# Metro_Mini_Rev_A.net
KiCad netlist of a schematic drawn in EAGLE
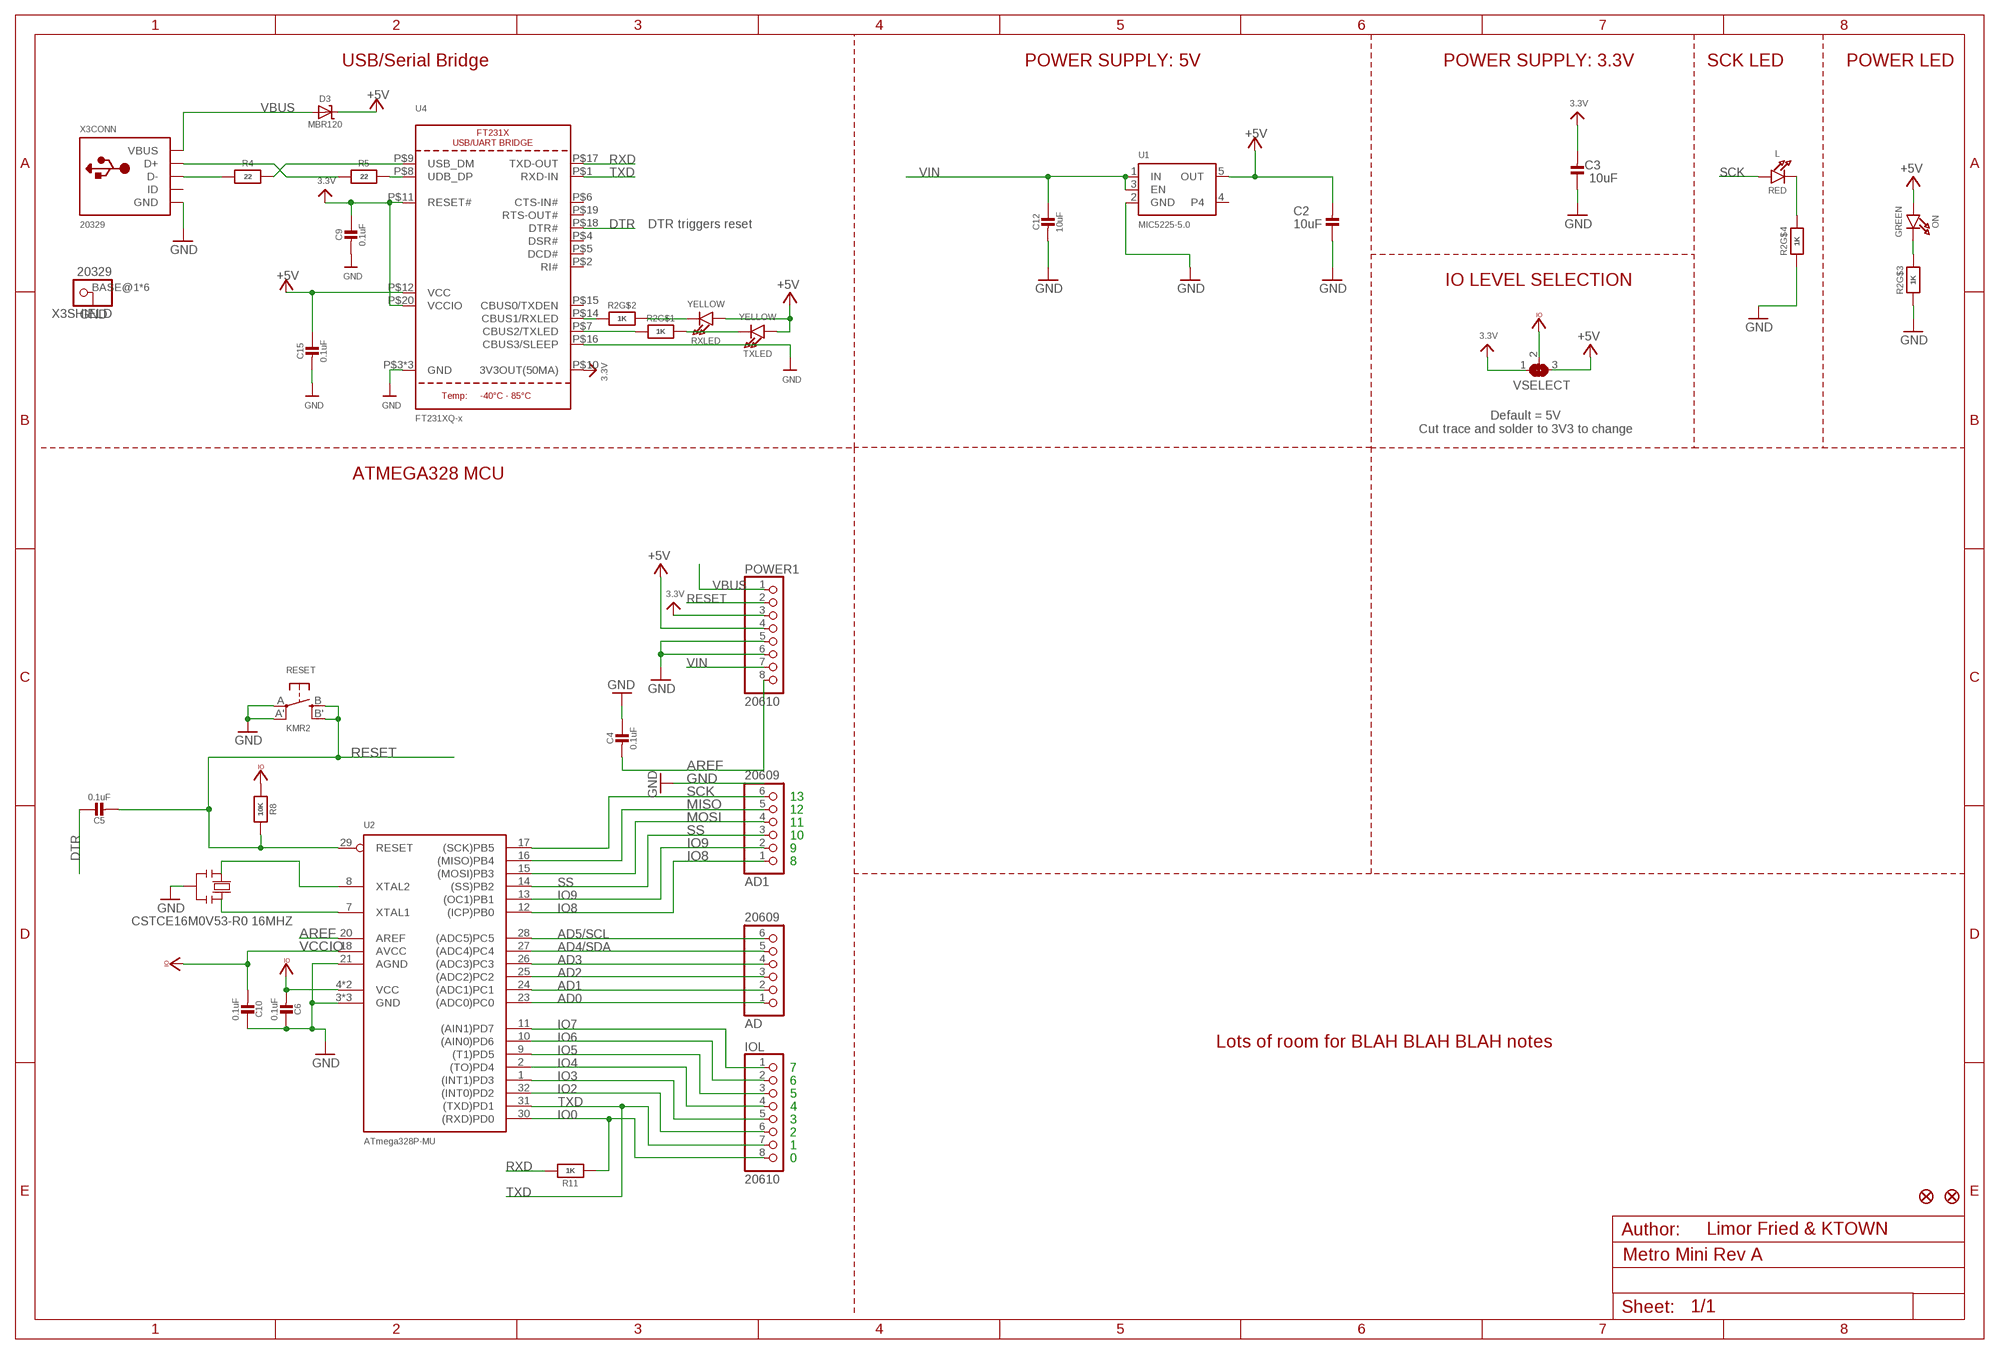
[diagram p0: schematic, sheet 1]

(export (version "E")
  (design (tool "Eeschema 10.0.6"))
  (components
    (comp (ref "AD")
      (value "20609")
      (footprint "eagle-import:1X06_ROUND")
      (libsource (lib "eagle-import") (part "HEADER-1X6ROUND"))
    )
    (comp (ref "AD1")
      (value "20609")
      (footprint "eagle-import:1X06_ROUND")
      (libsource (lib "eagle-import") (part "HEADER-1X6ROUND"))
    )
    (comp (ref "C2")
      (value "10uF")
      (footprint "eagle-import:0805-NO")
      (libsource (lib "eagle-import") (part "CAP_CERAMIC0805-NOOUTLINE"))
    )
    (comp (ref "C3")
      (value "10uF")
      (footprint "eagle-import:0805-NO")
      (libsource (lib "eagle-import") (part "CAP_CERAMIC0805-NOOUTLINE"))
    )
    (comp (ref "C4")
      (value "0.1uF")
      (footprint "eagle-import:0805-NO")
      (libsource (lib "eagle-import") (part "CAP_CERAMIC0805-NOOUTLINE"))
    )
    (comp (ref "C5")
      (value "0.1uF")
      (footprint "eagle-import:_0805MP")
      (libsource (lib "eagle-import") (part "CAP_CERAMIC_0805MP"))
    )
    (comp (ref "C6")
      (value "0.1uF")
      (footprint "eagle-import:0805-NO")
      (libsource (lib "eagle-import") (part "CAP_CERAMIC0805-NOOUTLINE"))
    )
    (comp (ref "C9")
      (value "0.1uF")
      (footprint "eagle-import:0805-NO")
      (libsource (lib "eagle-import") (part "CAP_CERAMIC0805-NOOUTLINE"))
    )
    (comp (ref "C10")
      (value "0.1uF")
      (footprint "eagle-import:0805-NO")
      (libsource (lib "eagle-import") (part "CAP_CERAMIC0805-NOOUTLINE"))
    )
    (comp (ref "C12")
      (value "10uF")
      (footprint "eagle-import:0805-NO")
      (libsource (lib "eagle-import") (part "CAP_CERAMIC0805-NOOUTLINE"))
    )
    (comp (ref "C15")
      (value "0.1uF")
      (footprint "eagle-import:0805-NO")
      (libsource (lib "eagle-import") (part "CAP_CERAMIC0805-NOOUTLINE"))
    )
    (comp (ref "D3")
      (value "MBR120")
      (footprint "eagle-import:SOD-123")
      (libsource (lib "eagle-import") (part "DIODE-SCHOTTKYSOD-123"))
    )
    (comp (ref "FD1")
      (value "FIDUCIAL\"\"")
      (footprint "eagle-import:FIDUCIAL_1MM")
      (libsource (lib "eagle-import") (part "FIDUCIAL{dblquote}{dblquote}"))
    )
    (comp (ref "FD2")
      (value "FIDUCIAL\"\"")
      (footprint "eagle-import:FIDUCIAL_1MM")
      (libsource (lib "eagle-import") (part "FIDUCIAL{dblquote}{dblquote}"))
    )
    (comp (ref "IOL")
      (value "20610")
      (footprint "eagle-import:1X08_ROUND")
      (libsource (lib "eagle-import") (part "HEADER-1X8ROUND"))
    )
    (comp (ref "L")
      (value "RED")
      (footprint "eagle-import:CHIPLED_0805_NOOUTLINE")
      (libsource (lib "eagle-import") (part "LED0805_NOOUTLINE"))
    )
    (comp (ref "ON")
      (value "GREEN")
      (footprint "eagle-import:CHIPLED_0805_NOOUTLINE")
      (libsource (lib "eagle-import") (part "LED0805_NOOUTLINE"))
    )
    (comp (ref "POWER1")
      (value "20610")
      (footprint "eagle-import:1X08_ROUND_70")
      (libsource (lib "eagle-import") (part "HEADER-1X870MIL"))
    )
    (comp (ref "R2")
      (value "1K")
      (footprint "eagle-import:RESPACK_4X0603")
      (libsource (lib "eagle-import") (part "RESISTOR_4PACK"))
    )
    (comp (ref "R4")
      (value "22")
      (footprint "eagle-import:0805-NO")
      (libsource (lib "eagle-import") (part "RESISTOR0805_NOOUTLINE"))
    )
    (comp (ref "R5")
      (value "22")
      (footprint "eagle-import:_0805MP")
      (libsource (lib "eagle-import") (part "RESISTOR_0805MP"))
    )
    (comp (ref "R8")
      (value "10K")
      (footprint "eagle-import:0805-NO")
      (libsource (lib "eagle-import") (part "RESISTOR0805_NOOUTLINE"))
    )
    (comp (ref "R11")
      (value "1K")
      (footprint "eagle-import:0805-NO")
      (libsource (lib "eagle-import") (part "RESISTOR0805_NOOUTLINE"))
    )
    (comp (ref "RESET")
      (value "KMR2")
      (footprint "eagle-import:BTN_KMR2_4.6X2.8")
      (libsource (lib "eagle-import") (part "SWITCH_TACT_SMT4.6X2.8"))
    )
    (comp (ref "RXLED")
      (value "YELLOW")
      (footprint "eagle-import:CHIPLED_0805_NOOUTLINE")
      (libsource (lib "eagle-import") (part "LED0805_NOOUTLINE"))
    )
    (comp (ref "TXLED")
      (value "YELLOW")
      (footprint "eagle-import:CHIPLED_0805_NOOUTLINE")
      (libsource (lib "eagle-import") (part "LED0805_NOOUTLINE"))
    )
    (comp (ref "U1")
      (value "MIC5225-5.0")
      (footprint "eagle-import:SOT23-5")
      (libsource (lib "eagle-import") (part "VREG_SOT23-5"))
    )
    (comp (ref "U2")
      (value "ATmega328P-MU")
      (footprint "eagle-import:MLF32-TH")
      (libsource (lib "eagle-import") (part "ATMEGA328P"))
    )
    (comp (ref "U4")
      (value "FT231XQ-x")
      (footprint "eagle-import:QFN20_4MM")
      (libsource (lib "eagle-import") (part "FT231X"))
    )
    (comp (ref "VSELECT")
      (value "SOLDERJUMPER_2WAY")
      (footprint "eagle-import:SOLDERJUMPER_2WAY_OPEN_NOPASTE")
      (libsource (lib "eagle-import") (part "SOLDERJUMPER_2WAY"))
    )
    (comp (ref "X3")
      (value "20329")
      (footprint "eagle-import:4UCONN_20329")
      (libsource (lib "eagle-import") (part "USB_W_SHIELD_20329"))
    )
    (comp (ref "Y2")
      (value "CSTCE16M0V53-R0 16MHZ")
      (footprint "eagle-import:RESONATOR")
      (libsource (lib "eagle-import") (part "RESONATORMU"))
    )
  )
  (nets
    (net (code "1") (name "+5V") (class "Default")
      (node (ref "C15") (pin "1") (pinfunction "1_1") (pintype "passive"))
      (node (ref "C2") (pin "2") (pinfunction "2_2") (pintype "passive"))
      (node (ref "D3") (pin "C") (pinfunction "C_C") (pintype "passive"))
      (node (ref "ON") (pin "A") (pinfunction "A_A") (pintype "passive"))
      (node (ref "POWER1") (pin "4") (pinfunction "4_4") (pintype "passive"))
      (node (ref "RXLED") (pin "A") (pinfunction "A_A") (pintype "passive"))
      (node (ref "TXLED") (pin "A") (pinfunction "A_A") (pintype "passive"))
      (node (ref "U1") (pin "5") (pinfunction "OUT_5") (pintype "power_in"))
      (node (ref "U4") (pin "P$12") (pinfunction "VCC_P$12") (pintype "power_in"))
      (node (ref "VSELECT") (pin "3") (pinfunction "3_3") (pintype "passive"))
    )
    (net (code "2") (name "/AD0") (class "Default")
      (node (ref "AD") (pin "1") (pinfunction "1_1") (pintype "passive"))
      (node (ref "U2") (pin "23") (pinfunction "(ADC0)PC0_23") (pintype "bidirectional"))
    )
    (net (code "3") (name "/AD1") (class "Default")
      (node (ref "AD") (pin "2") (pinfunction "2_2") (pintype "passive"))
      (node (ref "U2") (pin "24") (pinfunction "(ADC1)PC1_24") (pintype "bidirectional"))
    )
    (net (code "4") (name "/AD2") (class "Default")
      (node (ref "AD") (pin "3") (pinfunction "3_3") (pintype "passive"))
      (node (ref "U2") (pin "25") (pinfunction "(ADC2)PC2_25") (pintype "bidirectional"))
    )
    (net (code "5") (name "/AD3") (class "Default")
      (node (ref "AD") (pin "4") (pinfunction "4_4") (pintype "passive"))
      (node (ref "U2") (pin "26") (pinfunction "(ADC3)PC3_26") (pintype "bidirectional"))
    )
    (net (code "6") (name "/AD4{slash}SDA") (class "Default")
      (node (ref "AD") (pin "5") (pinfunction "5_5") (pintype "passive"))
      (node (ref "U2") (pin "27") (pinfunction "(ADC4)PC4_27") (pintype "bidirectional"))
    )
    (net (code "7") (name "/AD5{slash}SCL") (class "Default")
      (node (ref "AD") (pin "6") (pinfunction "6_6") (pintype "passive"))
      (node (ref "U2") (pin "28") (pinfunction "(ADC5)PC5_28") (pintype "bidirectional"))
    )
    (net (code "8") (name "/AREF") (class "Default")
      (node (ref "C4") (pin "2") (pinfunction "2_2") (pintype "passive"))
      (node (ref "POWER1") (pin "8") (pinfunction "8_8") (pintype "passive"))
      (node (ref "U2") (pin "20") (pinfunction "AREF_20") (pintype "power_in"))
    )
    (net (code "9") (name "/DTR") (class "Default")
      (node (ref "C5") (pin "1") (pinfunction "1_1") (pintype "passive"))
      (node (ref "U4") (pin "P$18") (pinfunction "DTR#_P$18") (pintype "output"))
    )
    (net (code "10") (name "/IO0") (class "Default")
      (node (ref "IOL") (pin "8") (pinfunction "8_8") (pintype "passive"))
      (node (ref "R11") (pin "1") (pinfunction "1_1") (pintype "passive"))
      (node (ref "U2") (pin "30") (pinfunction "(RXD)PD0_30") (pintype "bidirectional"))
    )
    (net (code "11") (name "/IO2") (class "Default")
      (node (ref "IOL") (pin "6") (pinfunction "6_6") (pintype "passive"))
      (node (ref "U2") (pin "32") (pinfunction "(INT0)PD2_32") (pintype "bidirectional"))
    )
    (net (code "12") (name "/IO3") (class "Default")
      (node (ref "IOL") (pin "5") (pinfunction "5_5") (pintype "passive"))
      (node (ref "U2") (pin "1") (pinfunction "(INT1)PD3_1") (pintype "bidirectional"))
    )
    (net (code "13") (name "/IO4") (class "Default")
      (node (ref "IOL") (pin "4") (pinfunction "4_4") (pintype "passive"))
      (node (ref "U2") (pin "2") (pinfunction "(TO)PD4_2") (pintype "bidirectional"))
    )
    (net (code "14") (name "/IO5") (class "Default")
      (node (ref "IOL") (pin "3") (pinfunction "3_3") (pintype "passive"))
      (node (ref "U2") (pin "9") (pinfunction "(T1)PD5_9") (pintype "bidirectional"))
    )
    (net (code "15") (name "/IO6") (class "Default")
      (node (ref "IOL") (pin "2") (pinfunction "2_2") (pintype "passive"))
      (node (ref "U2") (pin "10") (pinfunction "(AIN0)PD6_10") (pintype "bidirectional"))
    )
    (net (code "16") (name "/IO7") (class "Default")
      (node (ref "IOL") (pin "1") (pinfunction "1_1") (pintype "passive"))
      (node (ref "U2") (pin "11") (pinfunction "(AIN1)PD7_11") (pintype "bidirectional"))
    )
    (net (code "17") (name "/IO8") (class "Default")
      (node (ref "AD1") (pin "1") (pinfunction "1_1") (pintype "passive"))
      (node (ref "U2") (pin "12") (pinfunction "(ICP)PB0_12") (pintype "bidirectional"))
    )
    (net (code "18") (name "/IO9") (class "Default")
      (node (ref "AD1") (pin "2") (pinfunction "2_2") (pintype "passive"))
      (node (ref "U2") (pin "13") (pinfunction "(OC1)PB1_13") (pintype "bidirectional"))
    )
    (net (code "19") (name "/MISO") (class "Default")
      (node (ref "AD1") (pin "5") (pinfunction "5_5") (pintype "passive"))
      (node (ref "U2") (pin "16") (pinfunction "(MISO)PB4_16") (pintype "bidirectional"))
    )
    (net (code "20") (name "/MOSI") (class "Default")
      (node (ref "AD1") (pin "4") (pinfunction "4_4") (pintype "passive"))
      (node (ref "U2") (pin "15") (pinfunction "(MOSI)PB3_15") (pintype "bidirectional"))
    )
    (net (code "21") (name "/RESET") (class "Default")
      (node (ref "C5") (pin "2") (pinfunction "2_2") (pintype "passive"))
      (node (ref "POWER1") (pin "2") (pinfunction "2_2") (pintype "passive"))
      (node (ref "R8") (pin "1") (pinfunction "1_1") (pintype "passive"))
      (node (ref "RESET") (pin "B") (pinfunction "S_B") (pintype "passive"))
      (node (ref "RESET") (pin "B'") (pinfunction "S1_B'") (pintype "passive"))
      (node (ref "U2") (pin "29") (pinfunction "RESET_29") (pintype "bidirectional"))
    )
    (net (code "22") (name "/RXD") (class "Default")
      (node (ref "R11") (pin "2") (pinfunction "2_2") (pintype "passive"))
      (node (ref "U4") (pin "P$17") (pinfunction "TXD-OUT_P$17") (pintype "output"))
    )
    (net (code "23") (name "/SCK") (class "Default")
      (node (ref "AD1") (pin "6") (pinfunction "6_6") (pintype "passive"))
      (node (ref "L") (pin "A") (pinfunction "A_A") (pintype "passive"))
      (node (ref "U2") (pin "17") (pinfunction "(SCK)PB5_17") (pintype "bidirectional"))
    )
    (net (code "24") (name "/SS") (class "Default")
      (node (ref "AD1") (pin "3") (pinfunction "3_3") (pintype "passive"))
      (node (ref "U2") (pin "14") (pinfunction "(SS)PB2_14") (pintype "bidirectional"))
    )
    (net (code "25") (name "/TXD") (class "Default")
      (node (ref "IOL") (pin "7") (pinfunction "7_7") (pintype "passive"))
      (node (ref "U2") (pin "31") (pinfunction "(TXD)PD1_31") (pintype "bidirectional"))
      (node (ref "U4") (pin "P$1") (pinfunction "RXD-IN_P$1") (pintype "input"))
    )
    (net (code "26") (name "/VBUS") (class "Default")
      (node (ref "D3") (pin "A") (pinfunction "A_A") (pintype "passive"))
      (node (ref "POWER1") (pin "1") (pinfunction "1_1") (pintype "passive"))
      (node (ref "X3") (pin "VBUS") (pinfunction "VBUS_VBUS") (pintype "power_in"))
    )
    (net (code "27") (name "/VIN") (class "Default")
      (node (ref "C12") (pin "1") (pinfunction "1_1") (pintype "passive"))
      (node (ref "POWER1") (pin "7") (pinfunction "7_7") (pintype "passive"))
      (node (ref "U1") (pin "1") (pinfunction "IN_1") (pintype "power_in"))
      (node (ref "U1") (pin "3") (pinfunction "EN_3") (pintype "input"))
    )
    (net (code "28") (name "3.3V") (class "Default")
      (node (ref "C3") (pin "2") (pinfunction "2_2") (pintype "passive"))
      (node (ref "C9") (pin "1") (pinfunction "1_1") (pintype "passive"))
      (node (ref "POWER1") (pin "3") (pinfunction "3_3") (pintype "passive"))
      (node (ref "U4") (pin "P$10") (pinfunction "3V3OUT(50MA)_P$10") (pintype "power_in"))
      (node (ref "U4") (pin "P$11") (pinfunction "RESET#_P$11") (pintype "input"))
      (node (ref "U4") (pin "P$20") (pinfunction "VCCIO_P$20") (pintype "power_in"))
      (node (ref "VSELECT") (pin "1") (pinfunction "1_1") (pintype "passive"))
    )
    (net (code "29") (name "GND") (class "Default")
      (node (ref "C10") (pin "1") (pinfunction "1_1") (pintype "passive"))
      (node (ref "C12") (pin "2") (pinfunction "2_2") (pintype "passive"))
      (node (ref "C15") (pin "2") (pinfunction "2_2") (pintype "passive"))
      (node (ref "C2") (pin "1") (pinfunction "1_1") (pintype "passive"))
      (node (ref "C3") (pin "1") (pinfunction "1_1") (pintype "passive"))
      (node (ref "C4") (pin "1") (pinfunction "1_1") (pintype "passive"))
      (node (ref "C6") (pin "1") (pinfunction "1_1") (pintype "passive"))
      (node (ref "C9") (pin "2") (pinfunction "2_2") (pintype "passive"))
      (node (ref "POWER1") (pin "5") (pinfunction "5_5") (pintype "passive"))
      (node (ref "POWER1") (pin "6") (pinfunction "6_6") (pintype "passive"))
      (node (ref "R2") (pin "3") (pinfunction "1_3") (pintype "passive"))
      (node (ref "R2") (pin "4") (pinfunction "1_4") (pintype "passive"))
      (node (ref "RESET") (pin "A") (pinfunction "P_A") (pintype "passive"))
      (node (ref "RESET") (pin "A'") (pinfunction "P1_A'") (pintype "passive"))
      (node (ref "U1") (pin "2") (pinfunction "GND_2") (pintype "power_in"))
      (node (ref "U2") (pin "21") (pinfunction "AGND_21") (pintype "power_in"))
      (node (ref "U2") (pin "3") (pinfunction "GND_3") (pintype "power_in"))
      (node (ref "U2") (pin "5") (pinfunction "GND_5") (pintype "power_in"))
      (node (ref "U2") (pin "TH") (pinfunction "GND_TH") (pintype "power_in"))
      (node (ref "U4") (pin "P$13") (pinfunction "GND_P$13") (pintype "power_in"))
      (node (ref "U4") (pin "P$16") (pinfunction "CBUS3/SLEEP_P$16") (pintype "bidirectional"))
      (node (ref "U4") (pin "P$21") (pinfunction "GND_P$21") (pintype "power_in"))
      (node (ref "U4") (pin "P$3") (pinfunction "GND_P$3") (pintype "power_in"))
      (node (ref "X3") (pin "BASE@1") (pinfunction "1_BASE@1") (pintype "passive"))
      (node (ref "X3") (pin "BASE@2") (pinfunction "1_BASE@2") (pintype "passive"))
      (node (ref "X3") (pin "GND") (pinfunction "GND_GND") (pintype "power_in"))
      (node (ref "X3") (pin "SPRT@1") (pinfunction "1_SPRT@1") (pintype "passive"))
      (node (ref "X3") (pin "SPRT@2") (pinfunction "1_SPRT@2") (pintype "passive"))
      (node (ref "X3") (pin "SPRT@3") (pinfunction "1_SPRT@3") (pintype "passive"))
      (node (ref "X3") (pin "SPRT@4") (pinfunction "1_SPRT@4") (pintype "passive"))
      (node (ref "Y2") (pin "2") (pinfunction "2_2") (pintype "passive"))
    )
    (net (code "30") (name "Net-(R2A-2)") (class "Default")
      (node (ref "R2") (pin "8") (pinfunction "2_8") (pintype "passive"))
      (node (ref "TXLED") (pin "C") (pinfunction "C_C") (pintype "passive"))
    )
    (net (code "31") (name "Net-(R2B-1)") (class "Default")
      (node (ref "R2") (pin "2") (pinfunction "1_2") (pintype "passive"))
      (node (ref "U4") (pin "P$14") (pinfunction "CBUS1/RXLED_P$14") (pintype "bidirectional"))
    )
    (net (code "32") (name "Net-(R2B-2)") (class "Default")
      (node (ref "R2") (pin "7") (pinfunction "2_7") (pintype "passive"))
      (node (ref "RXLED") (pin "C") (pinfunction "C_C") (pintype "passive"))
    )
    (net (code "33") (name "Net-(R2C-2)") (class "Default")
      (node (ref "ON") (pin "C") (pinfunction "C_C") (pintype "passive"))
      (node (ref "R2") (pin "6") (pinfunction "2_6") (pintype "passive"))
    )
    (net (code "34") (name "Net-(R2D-2)") (class "Default")
      (node (ref "L") (pin "C") (pinfunction "C_C") (pintype "passive"))
      (node (ref "R2") (pin "5") (pinfunction "2_5") (pintype "passive"))
    )
    (net (code "35") (name "Net-(R4-Pad1)") (class "Default")
      (node (ref "R4") (pin "1") (pinfunction "1_1") (pintype "passive"))
      (node (ref "X3") (pin "D-") (pinfunction "D-_D-") (pintype "bidirectional"))
    )
    (net (code "36") (name "Net-(R5-Pad1)") (class "Default")
      (node (ref "R5") (pin "1") (pinfunction "1_1") (pintype "passive"))
      (node (ref "X3") (pin "D+") (pinfunction "D+_D+") (pintype "bidirectional"))
    )
    (net (code "37") (name "Net-(U2-XTAL1)") (class "Default")
      (node (ref "U2") (pin "7") (pinfunction "XTAL1_7") (pintype "bidirectional"))
      (node (ref "Y2") (pin "3") (pinfunction "3_3") (pintype "passive"))
    )
    (net (code "38") (name "Net-(U2-XTAL2)") (class "Default")
      (node (ref "U2") (pin "8") (pinfunction "XTAL2_8") (pintype "bidirectional"))
      (node (ref "Y2") (pin "1") (pinfunction "1_1") (pintype "passive"))
    )
    (net (code "39") (name "Net-(U4-CBUS2{slash}TXLED)") (class "Default")
      (node (ref "R2") (pin "1") (pinfunction "1_1") (pintype "passive"))
      (node (ref "U4") (pin "P$7") (pinfunction "CBUS2/TXLED_P$7") (pintype "bidirectional"))
    )
    (net (code "40") (name "Net-(U4-UDB_DP)") (class "Default")
      (node (ref "R5") (pin "2") (pinfunction "2_2") (pintype "passive"))
      (node (ref "U4") (pin "P$8") (pinfunction "UDB_DP_P$8") (pintype "input"))
    )
    (net (code "41") (name "Net-(U4-USB_DM)") (class "Default")
      (node (ref "R4") (pin "2") (pinfunction "2_2") (pintype "passive"))
      (node (ref "U4") (pin "P$9") (pinfunction "USB_DM_P$9") (pintype "input"))
    )
    (net (code "42") (name "VCCIO") (class "Default")
      (node (ref "C10") (pin "2") (pinfunction "2_2") (pintype "passive"))
      (node (ref "C6") (pin "2") (pinfunction "2_2") (pintype "passive"))
      (node (ref "R8") (pin "2") (pinfunction "2_2") (pintype "passive"))
      (node (ref "U2") (pin "18") (pinfunction "AVCC_18") (pintype "power_in"))
      (node (ref "U2") (pin "4") (pinfunction "VCC_4") (pintype "power_in"))
      (node (ref "U2") (pin "6") (pinfunction "VCC_6") (pintype "power_in"))
      (node (ref "VSELECT") (pin "2") (pinfunction "2_2") (pintype "passive"))
    )
    (net (code "43") (name "unconnected-(U1-P4-Pad4)") (class "Default")
      (node (ref "U1") (pin "4") (pinfunction "P4_4") (pintype "bidirectional"))
    )
    (net (code "44") (name "unconnected-(U4-CBUS0{slash}TXDEN-PadP$15)") (class "Default")
      (node (ref "U4") (pin "P$15") (pinfunction "CBUS0/TXDEN_P$15") (pintype "bidirectional"))
    )
    (net (code "45") (name "unconnected-(U4-CTS-IN#-PadP$6)") (class "Default")
      (node (ref "U4") (pin "P$6") (pinfunction "CTS-IN#_P$6") (pintype "input"))
    )
    (net (code "46") (name "unconnected-(U4-DCD#-PadP$5)") (class "Default")
      (node (ref "U4") (pin "P$5") (pinfunction "DCD#_P$5") (pintype "input"))
    )
    (net (code "47") (name "unconnected-(U4-DSR#-PadP$4)") (class "Default")
      (node (ref "U4") (pin "P$4") (pinfunction "DSR#_P$4") (pintype "input"))
    )
    (net (code "48") (name "unconnected-(U4-RI#-PadP$2)") (class "Default")
      (node (ref "U4") (pin "P$2") (pinfunction "RI#_P$2") (pintype "input"))
    )
    (net (code "49") (name "unconnected-(U4-RTS-OUT#-PadP$19)") (class "Default")
      (node (ref "U4") (pin "P$19") (pinfunction "RTS-OUT#_P$19") (pintype "output"))
    )
    (net (code "50") (name "unconnected-(X3-PadID)") (class "Default")
      (node (ref "X3") (pin "ID") (pinfunction "ID_ID") (pintype "bidirectional"))
    )
  )
)
